# RS485.net
KiCad netlist of a schematic drawn in Altium Designer
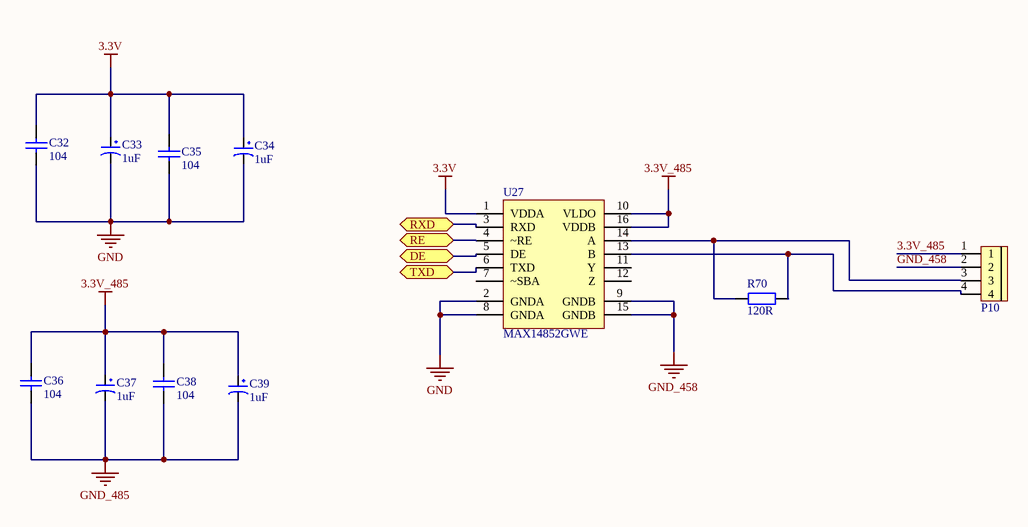
[diagram p0: RS485.SchDoc]

(export (version "E")
  (design (tool "Eeschema 10.0.6"))
  (components
    (comp (ref "C32")
      (value "104")
      (footprint "tu 0805")
      (description "Dán")
      (libsource (lib "Altium_Lib_by_KhueNguyenCreator") (part "Tu 0805 104 50V 10%"))
    )
    (comp (ref "C33")
      (value "1uF")
      (footprint "tu tantalum smd6032")
      (description "Dán")
      (libsource (lib "Altium_Lib_by_KhueNguyenCreator") (part "Tu tantalum 1uF 50V SMD6032"))
    )
    (comp (ref "C34")
      (value "1uF")
      (footprint "tu tantalum smd6032")
      (description "Dán")
      (libsource (lib "Altium_Lib_by_KhueNguyenCreator") (part "Tu tantalum 1uF 50V SMD6032"))
    )
    (comp (ref "C35")
      (value "104")
      (footprint "tu 0805")
      (description "Dán")
      (libsource (lib "Altium_Lib_by_KhueNguyenCreator") (part "Tu 0805 104 50V 10%"))
    )
    (comp (ref "C36")
      (value "104")
      (footprint "tu 0805")
      (description "Dán")
      (libsource (lib "Altium_Lib_by_KhueNguyenCreator") (part "Tu 0805 104 50V 10%"))
    )
    (comp (ref "C37")
      (value "1uF")
      (footprint "tu tantalum smd6032")
      (description "Dán")
      (libsource (lib "Altium_Lib_by_KhueNguyenCreator") (part "Tu tantalum 1uF 50V SMD6032"))
    )
    (comp (ref "C38")
      (value "104")
      (footprint "tu 0805")
      (description "Dán")
      (libsource (lib "Altium_Lib_by_KhueNguyenCreator") (part "Tu 0805 104 50V 10%"))
    )
    (comp (ref "C39")
      (value "1uF")
      (footprint "tu tantalum smd6032")
      (description "Dán")
      (libsource (lib "Altium_Lib_by_KhueNguyenCreator") (part "Tu tantalum 1uF 50V SMD6032"))
    )
    (comp (ref "P10")
      (value "CON 4 EDG5.08")
      (footprint "CON 4 4EDG5.08")
      (description "Cắm")
      (libsource (lib "Altium_Lib_by_KhueNguyenCreator") (part "CON 4 EDG5.08"))
    )
    (comp (ref "R70")
      (value "120R")
      (footprint "tro smd 0805")
      (description "Dán")
      (libsource (lib "Altium_Lib_by_KhueNguyenCreator") (part "Tro 0805 5% 120R"))
    )
    (comp (ref "U27")
      (value "MAX14852GWE")
      (footprint "SOICW16_50_440_25X76_SMT")
      (description "1/1 Transceiver Full RS422, RS485 16-SOIC")
      (fields (field (name "MANUFACTURER") "Maxim") (field (name "MANUFACTURER PART NUMBER") "MAX14852GWE+T"))
      (libsource (lib "Altium_Lib_by_KhueNguyenCreator") (part "IC_MAX14852GWE"))
    )
  )
  (nets
    (net (code "1") (name "/DE") (class "Default")
      (node (ref "U27") (pin "5") (pinfunction "DE_5") (pintype "passive"))
    )
    (net (code "2") (name "/RE") (class "Default")
      (node (ref "U27") (pin "4") (pinfunction "~RE_4") (pintype "passive"))
    )
    (net (code "3") (name "/RXD") (class "Default")
      (node (ref "U27") (pin "3") (pinfunction "RXD_3") (pintype "passive"))
    )
    (net (code "4") (name "/TXD") (class "Default")
      (node (ref "U27") (pin "6") (pinfunction "TXD_6") (pintype "passive"))
    )
    (net (code "5") (name "3.3V") (class "Default")
      (node (ref "C32") (pin "1") (pinfunction "1_1") (pintype "passive"))
      (node (ref "C33") (pin "1") (pinfunction "1_1") (pintype "passive"))
      (node (ref "C34") (pin "1") (pinfunction "1_1") (pintype "passive"))
      (node (ref "C35") (pin "1") (pinfunction "1_1") (pintype "passive"))
      (node (ref "U27") (pin "1") (pinfunction "VDDA_1") (pintype "passive"))
    )
    (net (code "6") (name "3.3V_485") (class "Default")
      (node (ref "C36") (pin "1") (pinfunction "1_1") (pintype "passive"))
      (node (ref "C37") (pin "1") (pinfunction "1_1") (pintype "passive"))
      (node (ref "C38") (pin "1") (pinfunction "1_1") (pintype "passive"))
      (node (ref "C39") (pin "1") (pinfunction "1_1") (pintype "passive"))
      (node (ref "P10") (pin "1") (pinfunction "1_1") (pintype "passive"))
      (node (ref "U27") (pin "10") (pinfunction "VLDO_10") (pintype "passive"))
      (node (ref "U27") (pin "16") (pinfunction "VDDB_16") (pintype "passive"))
    )
    (net (code "7") (name "GND") (class "Default")
      (node (ref "C32") (pin "2") (pinfunction "2_2") (pintype "passive"))
      (node (ref "C33") (pin "2") (pinfunction "2_2") (pintype "passive"))
      (node (ref "C34") (pin "2") (pinfunction "2_2") (pintype "passive"))
      (node (ref "C35") (pin "2") (pinfunction "2_2") (pintype "passive"))
      (node (ref "U27") (pin "2") (pinfunction "GNDA_2") (pintype "passive"))
      (node (ref "U27") (pin "8") (pinfunction "GNDA_8") (pintype "passive"))
    )
    (net (code "8") (name "GND_458") (class "Default")
      (node (ref "P10") (pin "2") (pinfunction "2_2") (pintype "passive"))
      (node (ref "U27") (pin "15") (pinfunction "GNDB_15") (pintype "passive"))
      (node (ref "U27") (pin "9") (pinfunction "GNDB_9") (pintype "passive"))
    )
    (net (code "9") (name "GND_485") (class "Default")
      (node (ref "C36") (pin "2") (pinfunction "2_2") (pintype "passive"))
      (node (ref "C37") (pin "2") (pinfunction "2_2") (pintype "passive"))
      (node (ref "C38") (pin "2") (pinfunction "2_2") (pintype "passive"))
      (node (ref "C39") (pin "2") (pinfunction "2_2") (pintype "passive"))
    )
    (net (code "10") (name "Net-(U27-A)") (class "Default")
      (node (ref "P10") (pin "3") (pinfunction "3_3") (pintype "passive"))
      (node (ref "R70") (pin "1") (pinfunction "1_1") (pintype "passive"))
      (node (ref "U27") (pin "14") (pinfunction "A_14") (pintype "passive"))
    )
    (net (code "11") (name "Net-(U27-B)") (class "Default")
      (node (ref "P10") (pin "4") (pinfunction "4_4") (pintype "passive"))
      (node (ref "R70") (pin "2") (pinfunction "2_2") (pintype "passive"))
      (node (ref "U27") (pin "13") (pinfunction "B_13") (pintype "passive"))
    )
    (net (code "12") (name "unconnected-(U27-Y-Pad11)") (class "Default")
      (node (ref "U27") (pin "11") (pinfunction "Y_11") (pintype "passive"))
    )
    (net (code "13") (name "unconnected-(U27-Z-Pad12)") (class "Default")
      (node (ref "U27") (pin "12") (pinfunction "Z_12") (pintype "passive"))
    )
    (net (code "14") (name "unconnected-(U27-~SBA-Pad7)") (class "Default")
      (node (ref "U27") (pin "7") (pinfunction "~SBA_7") (pintype "passive"))
    )
  )
)
